# sch.net
KiCad netlist of a schematic drawn in EasyEDA
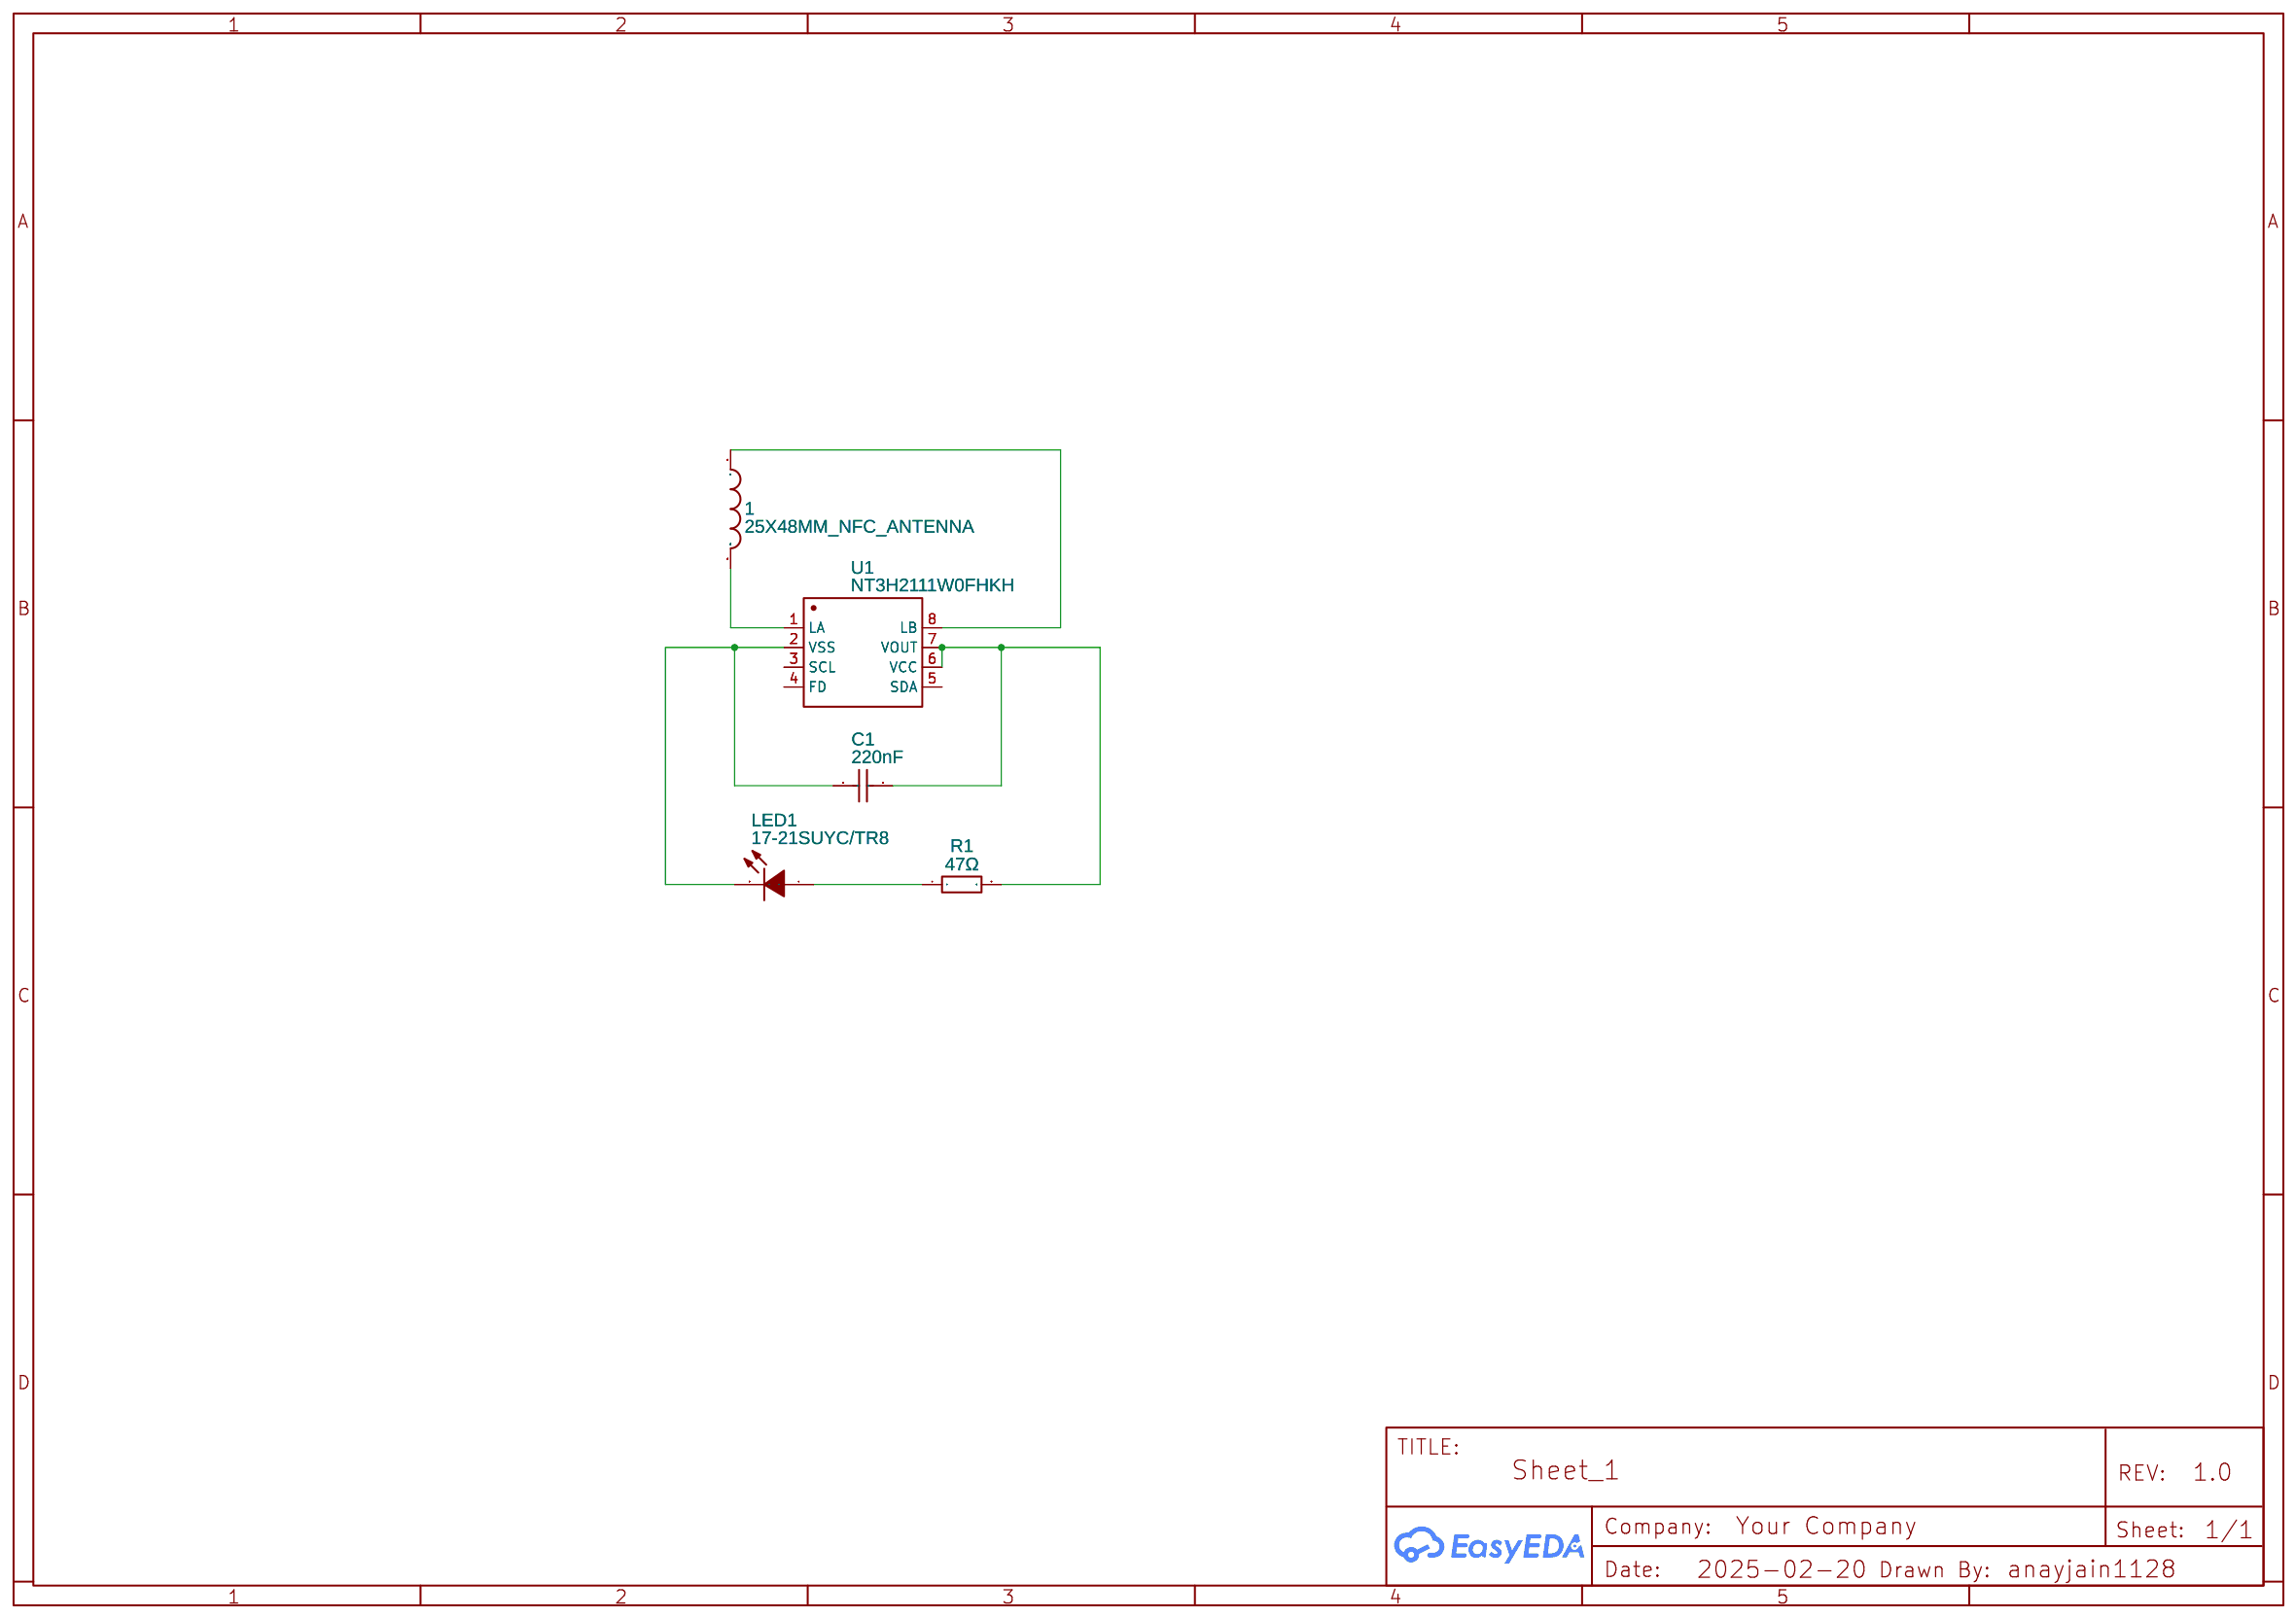
[diagram p0: schematic sheet]

(export (version "E")
  (design (tool "Eeschema 10.0.6"))
  (components
    (comp (ref "1") (value "25X48MM_NFC_ANTENNA") (libsource (lib "") (part "25X48MM_NFC_ANTENNA")))
    (comp (ref "C1")
      (value "220nF")
      (fields
        (field (name "Manufacturer Part") "CL10B224KA8NNNC")
        (field (name "Manufacturer") "SAMSUNG(三星)")
      )
      (libsource (lib "") (part "CL10B224KA8NNNC"))
    )
    (comp (ref "LED1")
      (value "17-21SUYC/TR8")
      (fields (field (name "Manufacturer Part") "KT-0805黄灯") (field (name "Manufacturer") "KENTO"))
      (libsource (lib "") (part "17-21SUYC/TR8"))
    )
    (comp (ref "R1")
      (value "47Ω")
      (fields
        (field (name "Manufacturer Part") "0603WAF470JT5E")
        (field (name "Manufacturer") "UNI-ROYAL(厚声)")
      )
      (libsource (lib "") (part "0603WAF470JT5E"))
    )
    (comp (ref "U1")
      (value "NT3H2111W0FHKH")
      (fields (field (name "Manufacturer") "NXP(恩智浦)"))
      (libsource (lib "") (part "NT3H2111W0FHKH"))
    )
  )
  (nets
    (net (code "1") (name "Net-(LED1-+)") (class "Default")
      (node (ref "LED1") (pin "1") (pinfunction "+_1") (pintype "unspecified"))
      (node (ref "R1") (pin "1") (pinfunction "1_1") (pintype "input"))
    )
    (net (code "2") (name "Net-(LED1--)") (class "Default")
      (node (ref "C1") (pin "1") (pinfunction "1_1") (pintype "input"))
      (node (ref "LED1") (pin "2") (pinfunction "-_2") (pintype "unspecified"))
      (node (ref "U1") (pin "2") (pinfunction "VSS_2") (pintype "unspecified"))
    )
    (net (code "3") (name "Net-(U1-LA)") (class "Default")
      (node (ref "1") (pin "P$2") (pinfunction "P$2_P$2") (pintype "bidirectional"))
      (node (ref "U1") (pin "1") (pinfunction "LA_1") (pintype "unspecified"))
    )
    (net (code "4") (name "Net-(U1-LB)") (class "Default")
      (node (ref "1") (pin "P$1") (pinfunction "P$1_P$1") (pintype "bidirectional"))
      (node (ref "U1") (pin "8") (pinfunction "LB_8") (pintype "unspecified"))
    )
    (net (code "5") (name "Net-(U1-VCC)") (class "Default")
      (node (ref "C1") (pin "2") (pinfunction "2_2") (pintype "input"))
      (node (ref "R1") (pin "2") (pinfunction "2_2") (pintype "input"))
      (node (ref "U1") (pin "6") (pinfunction "VCC_6") (pintype "unspecified"))
      (node (ref "U1") (pin "7") (pinfunction "VOUT_7") (pintype "unspecified"))
    )
    (net (code "6") (name "unconnected-(U1-FD-Pad4)") (class "Default")
      (node (ref "U1") (pin "4") (pinfunction "FD_4") (pintype "unspecified"))
    )
    (net (code "7") (name "unconnected-(U1-SCL-Pad3)") (class "Default")
      (node (ref "U1") (pin "3") (pinfunction "SCL_3") (pintype "unspecified"))
    )
    (net (code "8") (name "unconnected-(U1-SDA-Pad5)") (class "Default")
      (node (ref "U1") (pin "5") (pinfunction "SDA_5") (pintype "unspecified"))
    )
  )
)
